# Swagelock_controllerV2.net
KiCad netlist of a schematic drawn in EAGLE
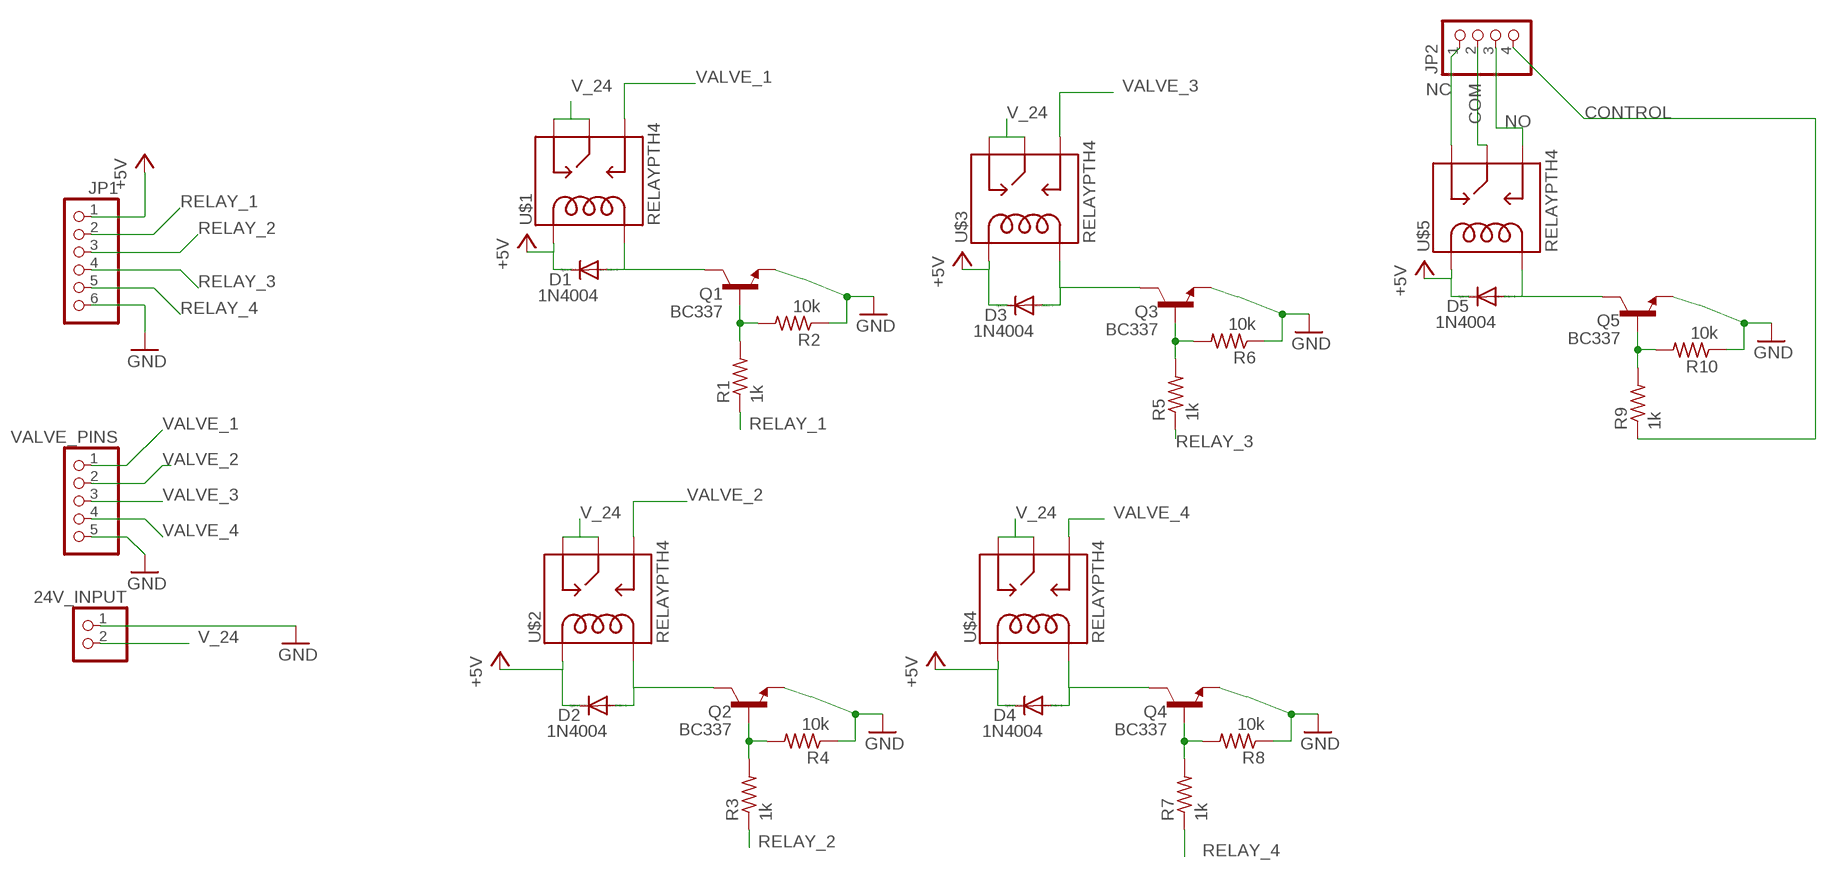
[diagram p0: schematic, sheet 1]

(export (version "E")
  (design (tool "Eeschema 10.0.6"))
  (components
    (comp (ref "24V_INPUT")
      (value "PINHD-1X2")
      (footprint "eagle-import:1X02")
      (libsource (lib "eagle-import") (part "PINHD-1X2"))
    )
    (comp (ref "D1")
      (value "1N4004")
      (footprint "eagle-import:DO41-10")
      (libsource (lib "eagle-import") (part "1N4004"))
    )
    (comp (ref "D2")
      (value "1N4004")
      (footprint "eagle-import:DO41-10")
      (libsource (lib "eagle-import") (part "1N4004"))
    )
    (comp (ref "D3")
      (value "1N4004")
      (footprint "eagle-import:DO41-10")
      (libsource (lib "eagle-import") (part "1N4004"))
    )
    (comp (ref "D4")
      (value "1N4004")
      (footprint "eagle-import:DO41-10")
      (libsource (lib "eagle-import") (part "1N4004"))
    )
    (comp (ref "D5")
      (value "1N4004")
      (footprint "eagle-import:DO41-10")
      (libsource (lib "eagle-import") (part "1N4004"))
    )
    (comp (ref "JP1")
      (value "PINHD-1X6")
      (footprint "eagle-import:1X06")
      (libsource (lib "eagle-import") (part "PINHD-1X6"))
    )
    (comp (ref "JP2")
      (value "PINHD-1X4")
      (footprint "eagle-import:1X04")
      (libsource (lib "eagle-import") (part "PINHD-1X4"))
    )
    (comp (ref "Q1")
      (value "BC337")
      (footprint "eagle-import:TO92")
      (libsource (lib "eagle-import") (part "BC337"))
    )
    (comp (ref "Q2")
      (value "BC337")
      (footprint "eagle-import:TO92")
      (libsource (lib "eagle-import") (part "BC337"))
    )
    (comp (ref "Q3")
      (value "BC337")
      (footprint "eagle-import:TO92")
      (libsource (lib "eagle-import") (part "BC337"))
    )
    (comp (ref "Q4")
      (value "BC337")
      (footprint "eagle-import:TO92")
      (libsource (lib "eagle-import") (part "BC337"))
    )
    (comp (ref "Q5")
      (value "BC337")
      (footprint "eagle-import:TO92")
      (libsource (lib "eagle-import") (part "BC337"))
    )
    (comp (ref "R1")
      (value "1k")
      (footprint "eagle-import:0204_5")
      (libsource (lib "eagle-import") (part "R-US_0204/5"))
    )
    (comp (ref "R2")
      (value "10k")
      (footprint "eagle-import:0204_5")
      (libsource (lib "eagle-import") (part "R-US_0204/5"))
    )
    (comp (ref "R3")
      (value "1k")
      (footprint "eagle-import:0204_5")
      (libsource (lib "eagle-import") (part "R-US_0204/5"))
    )
    (comp (ref "R4")
      (value "10k")
      (footprint "eagle-import:0204_5")
      (libsource (lib "eagle-import") (part "R-US_0204/5"))
    )
    (comp (ref "R5")
      (value "1k")
      (footprint "eagle-import:0204_5")
      (libsource (lib "eagle-import") (part "R-US_0204/5"))
    )
    (comp (ref "R6")
      (value "10k")
      (footprint "eagle-import:0204_5")
      (libsource (lib "eagle-import") (part "R-US_0204/5"))
    )
    (comp (ref "R7")
      (value "1k")
      (footprint "eagle-import:0204_5")
      (libsource (lib "eagle-import") (part "R-US_0204/5"))
    )
    (comp (ref "R8")
      (value "10k")
      (footprint "eagle-import:0204_5")
      (libsource (lib "eagle-import") (part "R-US_0204/5"))
    )
    (comp (ref "R9")
      (value "1k")
      (footprint "eagle-import:0204_5")
      (libsource (lib "eagle-import") (part "R-US_0204/5"))
    )
    (comp (ref "R10")
      (value "10k")
      (footprint "eagle-import:0204_5")
      (libsource (lib "eagle-import") (part "R-US_0204/5"))
    )
    (comp (ref "U$1")
      (value "RELAYPTH4")
      (footprint "eagle-import:RELAY-JZC")
      (libsource (lib "eagle-import") (part "RELAYPTH4"))
    )
    (comp (ref "U$2")
      (value "RELAYPTH4")
      (footprint "eagle-import:RELAY-JZC")
      (libsource (lib "eagle-import") (part "RELAYPTH4"))
    )
    (comp (ref "U$3")
      (value "RELAYPTH4")
      (footprint "eagle-import:RELAY-JZC")
      (libsource (lib "eagle-import") (part "RELAYPTH4"))
    )
    (comp (ref "U$4")
      (value "RELAYPTH4")
      (footprint "eagle-import:RELAY-JZC")
      (libsource (lib "eagle-import") (part "RELAYPTH4"))
    )
    (comp (ref "U$5")
      (value "RELAYPTH4")
      (footprint "eagle-import:RELAY-JZC")
      (libsource (lib "eagle-import") (part "RELAYPTH4"))
    )
    (comp (ref "VALVE_PINS")
      (value "PINHD-1X5")
      (footprint "eagle-import:1X05")
      (libsource (lib "eagle-import") (part "PINHD-1X5"))
    )
  )
  (nets
    (net (code "1") (name "+5V") (class "Default")
      (node (ref "D1") (pin "C") (pinfunction "C_C") (pintype "passive"))
      (node (ref "D2") (pin "C") (pinfunction "C_C") (pintype "passive"))
      (node (ref "D3") (pin "C") (pinfunction "C_C") (pintype "passive"))
      (node (ref "D4") (pin "C") (pinfunction "C_C") (pintype "passive"))
      (node (ref "D5") (pin "C") (pinfunction "C_C") (pintype "passive"))
      (node (ref "JP1") (pin "1") (pinfunction "1_1") (pintype "passive"))
      (node (ref "U$1") (pin "5") (pinfunction "COIL1_5") (pintype "bidirectional"))
      (node (ref "U$2") (pin "5") (pinfunction "COIL1_5") (pintype "bidirectional"))
      (node (ref "U$3") (pin "5") (pinfunction "COIL1_5") (pintype "bidirectional"))
      (node (ref "U$4") (pin "5") (pinfunction "COIL1_5") (pintype "bidirectional"))
      (node (ref "U$5") (pin "5") (pinfunction "COIL1_5") (pintype "bidirectional"))
    )
    (net (code "2") (name "COM") (class "Default")
      (node (ref "JP2") (pin "2") (pinfunction "2_2") (pintype "passive"))
      (node (ref "U$5") (pin "4") (pinfunction "MAIN_4") (pintype "bidirectional"))
    )
    (net (code "3") (name "CONTROL") (class "Default")
      (node (ref "JP2") (pin "4") (pinfunction "4_4") (pintype "passive"))
      (node (ref "R9") (pin "1") (pinfunction "1_1") (pintype "passive"))
    )
    (net (code "4") (name "GND") (class "Default")
      (node (ref "24V_INPUT") (pin "1") (pinfunction "1_1") (pintype "passive"))
      (node (ref "JP1") (pin "6") (pinfunction "6_6") (pintype "passive"))
      (node (ref "Q1") (pin "1") (pinfunction "E_1") (pintype "passive"))
      (node (ref "Q2") (pin "1") (pinfunction "E_1") (pintype "passive"))
      (node (ref "Q3") (pin "1") (pinfunction "E_1") (pintype "passive"))
      (node (ref "Q4") (pin "1") (pinfunction "E_1") (pintype "passive"))
      (node (ref "Q5") (pin "1") (pinfunction "E_1") (pintype "passive"))
      (node (ref "R10") (pin "1") (pinfunction "1_1") (pintype "passive"))
      (node (ref "R2") (pin "1") (pinfunction "1_1") (pintype "passive"))
      (node (ref "R4") (pin "1") (pinfunction "1_1") (pintype "passive"))
      (node (ref "R6") (pin "1") (pinfunction "1_1") (pintype "passive"))
      (node (ref "R8") (pin "1") (pinfunction "1_1") (pintype "passive"))
      (node (ref "VALVE_PINS") (pin "5") (pinfunction "5_5") (pintype "passive"))
    )
    (net (code "5") (name "NC") (class "Default")
      (node (ref "JP2") (pin "1") (pinfunction "1_1") (pintype "passive"))
      (node (ref "U$5") (pin "2") (pinfunction "NC_2") (pintype "bidirectional"))
    )
    (net (code "6") (name "NO") (class "Default")
      (node (ref "JP2") (pin "3") (pinfunction "3_3") (pintype "passive"))
      (node (ref "U$5") (pin "3") (pinfunction "NO_3") (pintype "bidirectional"))
    )
    (net (code "7") (name "Net-(Q1-B)") (class "Default")
      (node (ref "Q1") (pin "2") (pinfunction "B_2") (pintype "passive"))
      (node (ref "R1") (pin "2") (pinfunction "2_2") (pintype "passive"))
      (node (ref "R2") (pin "2") (pinfunction "2_2") (pintype "passive"))
    )
    (net (code "8") (name "Net-(Q1-C)") (class "Default")
      (node (ref "D1") (pin "A") (pinfunction "A_A") (pintype "passive"))
      (node (ref "Q1") (pin "3") (pinfunction "C_3") (pintype "passive"))
      (node (ref "U$1") (pin "1") (pinfunction "COIL2_1") (pintype "bidirectional"))
    )
    (net (code "9") (name "Net-(Q2-B)") (class "Default")
      (node (ref "Q2") (pin "2") (pinfunction "B_2") (pintype "passive"))
      (node (ref "R3") (pin "2") (pinfunction "2_2") (pintype "passive"))
      (node (ref "R4") (pin "2") (pinfunction "2_2") (pintype "passive"))
    )
    (net (code "10") (name "Net-(Q2-C)") (class "Default")
      (node (ref "D2") (pin "A") (pinfunction "A_A") (pintype "passive"))
      (node (ref "Q2") (pin "3") (pinfunction "C_3") (pintype "passive"))
      (node (ref "U$2") (pin "1") (pinfunction "COIL2_1") (pintype "bidirectional"))
    )
    (net (code "11") (name "Net-(Q3-B)") (class "Default")
      (node (ref "Q3") (pin "2") (pinfunction "B_2") (pintype "passive"))
      (node (ref "R5") (pin "2") (pinfunction "2_2") (pintype "passive"))
      (node (ref "R6") (pin "2") (pinfunction "2_2") (pintype "passive"))
    )
    (net (code "12") (name "Net-(Q3-C)") (class "Default")
      (node (ref "D3") (pin "A") (pinfunction "A_A") (pintype "passive"))
      (node (ref "Q3") (pin "3") (pinfunction "C_3") (pintype "passive"))
      (node (ref "U$3") (pin "1") (pinfunction "COIL2_1") (pintype "bidirectional"))
    )
    (net (code "13") (name "Net-(Q4-B)") (class "Default")
      (node (ref "Q4") (pin "2") (pinfunction "B_2") (pintype "passive"))
      (node (ref "R7") (pin "2") (pinfunction "2_2") (pintype "passive"))
      (node (ref "R8") (pin "2") (pinfunction "2_2") (pintype "passive"))
    )
    (net (code "14") (name "Net-(Q4-C)") (class "Default")
      (node (ref "D4") (pin "A") (pinfunction "A_A") (pintype "passive"))
      (node (ref "Q4") (pin "3") (pinfunction "C_3") (pintype "passive"))
      (node (ref "U$4") (pin "1") (pinfunction "COIL2_1") (pintype "bidirectional"))
    )
    (net (code "15") (name "Net-(Q5-B)") (class "Default")
      (node (ref "Q5") (pin "2") (pinfunction "B_2") (pintype "passive"))
      (node (ref "R10") (pin "2") (pinfunction "2_2") (pintype "passive"))
      (node (ref "R9") (pin "2") (pinfunction "2_2") (pintype "passive"))
    )
    (net (code "16") (name "Net-(Q5-C)") (class "Default")
      (node (ref "D5") (pin "A") (pinfunction "A_A") (pintype "passive"))
      (node (ref "Q5") (pin "3") (pinfunction "C_3") (pintype "passive"))
      (node (ref "U$5") (pin "1") (pinfunction "COIL2_1") (pintype "bidirectional"))
    )
    (net (code "17") (name "RELAY_1") (class "Default")
      (node (ref "JP1") (pin "2") (pinfunction "2_2") (pintype "passive"))
      (node (ref "R1") (pin "1") (pinfunction "1_1") (pintype "passive"))
    )
    (net (code "18") (name "RELAY_2") (class "Default")
      (node (ref "JP1") (pin "3") (pinfunction "3_3") (pintype "passive"))
      (node (ref "R3") (pin "1") (pinfunction "1_1") (pintype "passive"))
    )
    (net (code "19") (name "RELAY_3") (class "Default")
      (node (ref "JP1") (pin "4") (pinfunction "4_4") (pintype "passive"))
      (node (ref "R5") (pin "1") (pinfunction "1_1") (pintype "passive"))
    )
    (net (code "20") (name "RELAY_4") (class "Default")
      (node (ref "JP1") (pin "5") (pinfunction "5_5") (pintype "passive"))
      (node (ref "R7") (pin "1") (pinfunction "1_1") (pintype "passive"))
    )
    (net (code "21") (name "VALVE_1") (class "Default")
      (node (ref "U$1") (pin "3") (pinfunction "NO_3") (pintype "bidirectional"))
      (node (ref "VALVE_PINS") (pin "1") (pinfunction "1_1") (pintype "passive"))
    )
    (net (code "22") (name "VALVE_2") (class "Default")
      (node (ref "U$2") (pin "3") (pinfunction "NO_3") (pintype "bidirectional"))
      (node (ref "VALVE_PINS") (pin "2") (pinfunction "2_2") (pintype "passive"))
    )
    (net (code "23") (name "VALVE_3") (class "Default")
      (node (ref "U$3") (pin "3") (pinfunction "NO_3") (pintype "bidirectional"))
      (node (ref "VALVE_PINS") (pin "3") (pinfunction "3_3") (pintype "passive"))
    )
    (net (code "24") (name "VALVE_4") (class "Default")
      (node (ref "U$4") (pin "3") (pinfunction "NO_3") (pintype "bidirectional"))
      (node (ref "VALVE_PINS") (pin "4") (pinfunction "4_4") (pintype "passive"))
    )
    (net (code "25") (name "V_24") (class "Default")
      (node (ref "24V_INPUT") (pin "2") (pinfunction "2_2") (pintype "passive"))
      (node (ref "U$1") (pin "2") (pinfunction "NC_2") (pintype "bidirectional"))
      (node (ref "U$1") (pin "4") (pinfunction "MAIN_4") (pintype "bidirectional"))
      (node (ref "U$2") (pin "2") (pinfunction "NC_2") (pintype "bidirectional"))
      (node (ref "U$2") (pin "4") (pinfunction "MAIN_4") (pintype "bidirectional"))
      (node (ref "U$3") (pin "2") (pinfunction "NC_2") (pintype "bidirectional"))
      (node (ref "U$3") (pin "4") (pinfunction "MAIN_4") (pintype "bidirectional"))
      (node (ref "U$4") (pin "2") (pinfunction "NC_2") (pintype "bidirectional"))
      (node (ref "U$4") (pin "4") (pinfunction "MAIN_4") (pintype "bidirectional"))
    )
  )
)
